# openSX70_ALADDIN_V391SEEED_20180205.net
KiCad netlist of a schematic drawn in EAGLE
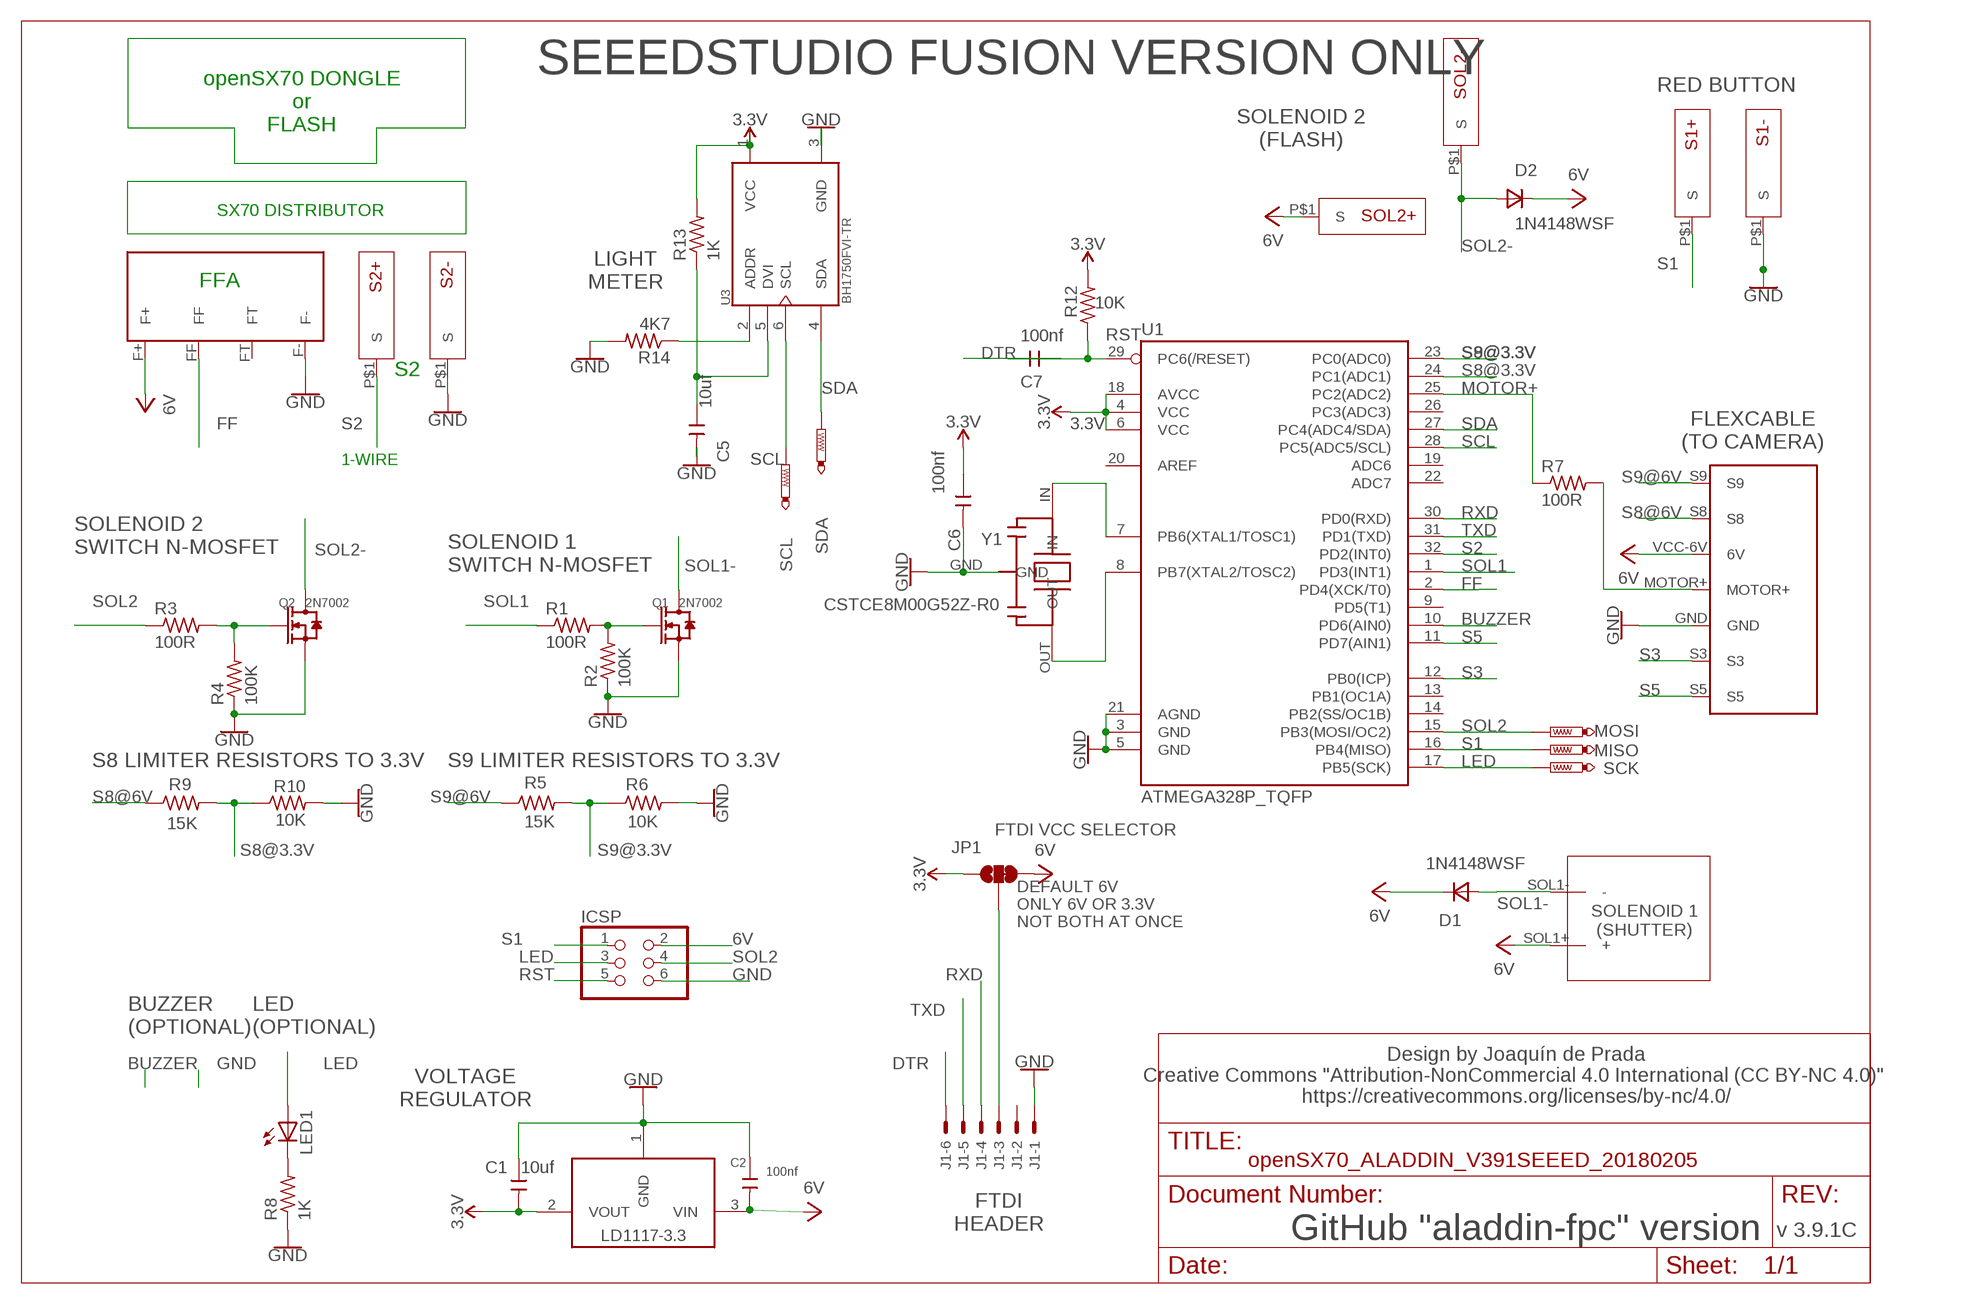
[diagram p0: schematic, sheet 1]

(export (version "E")
  (design (tool "Eeschema 10.0.6"))
  (components
    (comp (ref "C1")
      (value "10uf")
      (footprint "eagle-import:C0603")
      (fields (field (name "MPN") "CC0603KRX5R6BB106"))
      (libsource (lib "eagle-import") (part "CERAMIC-10UF-10V-10%-X5R(0603)"))
    )
    (comp (ref "C2")
      (value "100nf")
      (footprint "eagle-import:C0603")
      (fields (field (name "MPN") "CC0603KRX7R9BB104"))
      (libsource (lib "eagle-import") (part "CERAMIC-100NF-50V-10%-X7R(0603)"))
    )
    (comp (ref "C5")
      (value "10uf")
      (footprint "eagle-import:C0603")
      (fields (field (name "MPN") "CC0603KRX5R6BB106"))
      (libsource (lib "eagle-import") (part "CERAMIC-10UF-10V-10%-X5R(0603)"))
    )
    (comp (ref "C6")
      (value "100nf")
      (footprint "eagle-import:C0603")
      (fields (field (name "MPN") "CC0603KRX7R9BB104"))
      (libsource (lib "eagle-import") (part "CERAMIC-100NF-50V-10%-X7R(0603)"))
    )
    (comp (ref "C7")
      (value "100nf")
      (footprint "eagle-import:C0603")
      (fields (field (name "MPN") "CC0603KRX7R9BB104"))
      (libsource (lib "eagle-import") (part "CERAMIC-100NF-50V-10%-X7R(0603)"))
    )
    (comp (ref "D1")
      (value "1N4148WSF")
      (footprint "eagle-import:SOD323")
      (fields (field (name "MPN") "CDSOD323-T05C"))
      (libsource (lib "eagle-import") (part "DSOD323"))
    )
    (comp (ref "D2")
      (value "1N4148WSF")
      (footprint "eagle-import:SOD323")
      (fields (field (name "MPN") "CDSOD323-T05C"))
      (libsource (lib "eagle-import") (part "DSOD323"))
    )
    (comp (ref "ICSP")
      (value "PINHD-2X3")
      (footprint "eagle-import:2X03")
      (libsource (lib "eagle-import") (part "PINHD-2X3"))
    )
    (comp (ref "J1")
      (value "GND")
      (footprint "eagle-import:XF2L-0625-1")
      (fields (field (name "MF") "OMRON COMPONENTS USA") (field (name "MPN") "XF2L-0625-1"))
      (libsource (lib "eagle-import") (part "XF2-06?25-1L"))
    )
    (comp (ref "JP1")
      (value "FTDI VCC SELECTOR")
      (footprint "eagle-import:SMT-JUMPER_3_1-NC_TRACE_SILK")
      (libsource (lib "eagle-import") (part "JUMPER-SMT_3_1-NC_TRACE_SILK"))
    )
    (comp (ref "LD11172.5V")
      (value "LD1117 2.5V")
      (footprint "eagle-import:SOT223")
      (fields (field (name "MF") "Advanced Monolithic Systems") (field (name "MP") "AMS1117-5.0"))
      (libsource (lib "eagle-import") (part "LD1117-3.3"))
    )
    (comp (ref "LED1")
      (value "LEDCHIPLED_0805")
      (footprint "eagle-import:CHIPLED_0805")
      (libsource (lib "eagle-import") (part "LEDCHIPLED_0805"))
    )
    (comp (ref "MISO")
      (value "PTR1TP08R")
      (footprint "eagle-import:TP08R")
      (libsource (lib "eagle-import") (part "PTR1TP08R"))
    )
    (comp (ref "MOSI")
      (value "PTR1TP08R")
      (footprint "eagle-import:TP08R")
      (libsource (lib "eagle-import") (part "PTR1TP08R"))
    )
    (comp (ref "Q1")
      (value "2N7002")
      (footprint "eagle-import:SOT-23")
      (fields (field (name "MPN") "2N7002,215"))
      (libsource (lib "eagle-import") (part "SMD-MOSFET-N-CH-60V-300MA-LOGIC-LEVEL-FET-2N7002(SOT-23)"))
    )
    (comp (ref "Q2")
      (value "2N7002")
      (footprint "eagle-import:SOT-23")
      (fields (field (name "MPN") "2N7002,215"))
      (libsource (lib "eagle-import") (part "SMD-MOSFET-N-CH-60V-300MA-LOGIC-LEVEL-FET-2N7002(SOT-23)"))
    )
    (comp (ref "R1")
      (value "100R")
      (footprint "eagle-import:R0603")
      (libsource (lib "eagle-import") (part "R-US_R0603"))
    )
    (comp (ref "R2")
      (value "100K")
      (footprint "eagle-import:R0603")
      (libsource (lib "eagle-import") (part "R-US_R0603"))
    )
    (comp (ref "R3")
      (value "100R")
      (footprint "eagle-import:R0603")
      (libsource (lib "eagle-import") (part "R-US_R0603"))
    )
    (comp (ref "R4")
      (value "100K")
      (footprint "eagle-import:R0603")
      (libsource (lib "eagle-import") (part "R-US_R0603"))
    )
    (comp (ref "R5")
      (value "15K")
      (footprint "eagle-import:R0603")
      (libsource (lib "eagle-import") (part "R-US_R0603"))
    )
    (comp (ref "R6")
      (value "10K")
      (footprint "eagle-import:R0603")
      (libsource (lib "eagle-import") (part "R-US_R0603"))
    )
    (comp (ref "R7")
      (value "100R")
      (footprint "eagle-import:R0603")
      (libsource (lib "eagle-import") (part "R-US_R0603"))
    )
    (comp (ref "R8")
      (value "1K")
      (footprint "eagle-import:R0603")
      (libsource (lib "eagle-import") (part "R-US_R0603"))
    )
    (comp (ref "R9")
      (value "15K")
      (footprint "eagle-import:R0603")
      (libsource (lib "eagle-import") (part "R-US_R0603"))
    )
    (comp (ref "R10")
      (value "10K")
      (footprint "eagle-import:R0603")
      (libsource (lib "eagle-import") (part "R-US_R0603"))
    )
    (comp (ref "R12")
      (value "10K")
      (footprint "eagle-import:R0603")
      (libsource (lib "eagle-import") (part "R-US_R0603"))
    )
    (comp (ref "R13")
      (value "1K")
      (footprint "eagle-import:R0603")
      (libsource (lib "eagle-import") (part "R-US_R0603"))
    )
    (comp (ref "R14")
      (value "4K7")
      (footprint "eagle-import:R0603")
      (libsource (lib "eagle-import") (part "R-US_R0603"))
    )
    (comp (ref "S1+")
      (value "SX70-S-PAD-NEW")
      (footprint "eagle-import:SX70-S-PAD2")
      (libsource (lib "eagle-import") (part "SX70-S-PAD-NEW"))
    )
    (comp (ref "S1-")
      (value "SX70-S-PAD-NEW")
      (footprint "eagle-import:SX70-S-PAD2")
      (libsource (lib "eagle-import") (part "SX70-S-PAD-NEW"))
    )
    (comp (ref "S2+")
      (value "SX70-S-PAD-NEW")
      (footprint "eagle-import:SX70-S-PAD2")
      (libsource (lib "eagle-import") (part "SX70-S-PAD-NEW"))
    )
    (comp (ref "S2-")
      (value "SX70-S-PAD-NEW")
      (footprint "eagle-import:SX70-S-PAD2")
      (libsource (lib "eagle-import") (part "SX70-S-PAD-NEW"))
    )
    (comp (ref "SCK")
      (value "PTR1TP08R")
      (footprint "eagle-import:TP08R")
      (libsource (lib "eagle-import") (part "PTR1TP08R"))
    )
    (comp (ref "SCL")
      (value "PTR1TP08R")
      (footprint "eagle-import:TP08R")
      (libsource (lib "eagle-import") (part "PTR1TP08R"))
    )
    (comp (ref "SDA")
      (value "PTR1TP08R")
      (footprint "eagle-import:TP08R")
      (libsource (lib "eagle-import") (part "PTR1TP08R"))
    )
    (comp (ref "SOL1")
      (value "SX70-SOLENOID1-2PADS")
      (footprint "eagle-import:SX70-SOLENOID1-2")
      (libsource (lib "eagle-import") (part "SX70-SOLENOID1-2PADS"))
    )
    (comp (ref "SOL2+")
      (value "SX70-S-PAD-NEW")
      (footprint "eagle-import:SX70-S-PAD2")
      (libsource (lib "eagle-import") (part "SX70-S-PAD-NEW"))
    )
    (comp (ref "SOL2-")
      (value "SX70-S-PAD-NEW")
      (footprint "eagle-import:SX70-S-PAD2")
      (libsource (lib "eagle-import") (part "SX70-S-PAD-NEW"))
    )
    (comp (ref "U$1")
      (value "SX70-7-PAD")
      (footprint "eagle-import:SX70-7-PAD")
      (libsource (lib "eagle-import") (part "SX70-7-PAD"))
    )
    (comp (ref "U$2")
      (value "FFA")
      (footprint "eagle-import:FFA-PAD-PACKAGE")
      (libsource (lib "eagle-import") (part "SX70-FFA-PAD"))
    )
    (comp (ref "U1")
      (value "ATMEGA328P_TQFP")
      (footprint "eagle-import:TQFP32-08")
      (libsource (lib "eagle-import") (part "ATMEGA328P_TQFP"))
    )
    (comp (ref "U3")
      (value "BH1750FVI-TR")
      (footprint "eagle-import:SOTFL50P300X75-6N")
      (fields (field (name "MF") "Rohm"))
      (libsource (lib "eagle-import") (part "BH1750FVI-TR"))
    )
    (comp (ref "Y1")
      (value "CSTCE8M00G52Z-R0")
      (footprint "eagle-import:CFP95P160X100-3N")
      (fields (field (name "MF") "Murata") (field (name "MP") "CSTCE16M0V53-R0"))
      (libsource (lib "eagle-import") (part "CSTCE16M0V53-R0"))
    )
  )
  (nets
    (net (code "1") (name "/BUZZER") (class "Default")
      (node (ref "U1") (pin "10") (pinfunction "PD6(AIN0)_10") (pintype "bidirectional"))
    )
    (net (code "2") (name "/DTR") (class "Default")
      (node (ref "C7") (pin "1") (pinfunction "1_1") (pintype "passive"))
      (node (ref "J1") (pin "6") (pinfunction "MS_6") (pintype "passive"))
    )
    (net (code "3") (name "/FF") (class "Default")
      (node (ref "U$2") (pin "FF") (pinfunction "FF_FF") (pintype "bidirectional"))
      (node (ref "U1") (pin "2") (pinfunction "PD4(XCK/T0)_2") (pintype "bidirectional"))
    )
    (net (code "4") (name "/LED") (class "Default")
      (node (ref "ICSP") (pin "3") (pinfunction "3_3") (pintype "passive"))
      (node (ref "LED1") (pin "A") (pinfunction "A_A") (pintype "passive"))
      (node (ref "SCK") (pin "TP") (pinfunction "TP_TP") (pintype "input"))
      (node (ref "U1") (pin "17") (pinfunction "PB5(SCK)_17") (pintype "bidirectional"))
    )
    (net (code "5") (name "/MOTOR+") (class "Default")
      (node (ref "R7") (pin "1") (pinfunction "1_1") (pintype "passive"))
      (node (ref "U1") (pin "25") (pinfunction "PC2(ADC2)_25") (pintype "bidirectional"))
    )
    (net (code "6") (name "/RST") (class "Default")
      (node (ref "C7") (pin "2") (pinfunction "2_2") (pintype "passive"))
      (node (ref "ICSP") (pin "5") (pinfunction "5_5") (pintype "passive"))
      (node (ref "R12") (pin "1") (pinfunction "1_1") (pintype "passive"))
      (node (ref "U1") (pin "29") (pinfunction "PC6(/RESET)_29") (pintype "bidirectional"))
    )
    (net (code "7") (name "/RXD") (class "Default")
      (node (ref "J1") (pin "4") (pinfunction "MS_4") (pintype "passive"))
      (node (ref "U1") (pin "30") (pinfunction "PD0(RXD)_30") (pintype "bidirectional"))
    )
    (net (code "8") (name "/S1") (class "Default")
      (node (ref "ICSP") (pin "1") (pinfunction "1_1") (pintype "passive"))
      (node (ref "MISO") (pin "TP") (pinfunction "TP_TP") (pintype "input"))
      (node (ref "S1+") (pin "P$1") (pinfunction "S_P$1") (pintype "bidirectional"))
      (node (ref "U1") (pin "16") (pinfunction "PB4(MISO)_16") (pintype "bidirectional"))
    )
    (net (code "9") (name "/S2") (class "Default")
      (node (ref "S2+") (pin "P$1") (pinfunction "S_P$1") (pintype "bidirectional"))
      (node (ref "U1") (pin "32") (pinfunction "PD2(INT0)_32") (pintype "bidirectional"))
    )
    (net (code "10") (name "/S3") (class "Default")
      (node (ref "U$1") (pin "S3") (pinfunction "S3_S3") (pintype "bidirectional"))
      (node (ref "U1") (pin "12") (pinfunction "PB0(ICP)_12") (pintype "bidirectional"))
    )
    (net (code "11") (name "/S5") (class "Default")
      (node (ref "U$1") (pin "S5") (pinfunction "S5_S5") (pintype "bidirectional"))
      (node (ref "U1") (pin "11") (pinfunction "PD7(AIN1)_11") (pintype "bidirectional"))
    )
    (net (code "12") (name "/S8@3.3V") (class "Default")
      (node (ref "R10") (pin "1") (pinfunction "1_1") (pintype "passive"))
      (node (ref "R9") (pin "2") (pinfunction "2_2") (pintype "passive"))
      (node (ref "U1") (pin "24") (pinfunction "PC1(ADC1)_24") (pintype "bidirectional"))
    )
    (net (code "13") (name "/S8@6V") (class "Default")
      (node (ref "R9") (pin "1") (pinfunction "1_1") (pintype "passive"))
      (node (ref "U$1") (pin "S8") (pinfunction "S8_S8") (pintype "bidirectional"))
    )
    (net (code "14") (name "/S9@3.3V") (class "Default")
      (node (ref "R5") (pin "2") (pinfunction "2_2") (pintype "passive"))
      (node (ref "R6") (pin "1") (pinfunction "1_1") (pintype "passive"))
      (node (ref "U1") (pin "23") (pinfunction "PC0(ADC0)_23") (pintype "bidirectional"))
    )
    (net (code "15") (name "/S9@6V") (class "Default")
      (node (ref "R5") (pin "1") (pinfunction "1_1") (pintype "passive"))
      (node (ref "U$1") (pin "S9") (pinfunction "S9_S9") (pintype "bidirectional"))
    )
    (net (code "16") (name "/SCL") (class "Default")
      (node (ref "SCL") (pin "TP") (pinfunction "TP_TP") (pintype "input"))
      (node (ref "U1") (pin "28") (pinfunction "PC5(ADC5/SCL)_28") (pintype "bidirectional"))
      (node (ref "U3") (pin "6") (pinfunction "SCL_6") (pintype "input"))
    )
    (net (code "17") (name "/SDA") (class "Default")
      (node (ref "SDA") (pin "TP") (pinfunction "TP_TP") (pintype "input"))
      (node (ref "U1") (pin "27") (pinfunction "PC4(ADC4/SDA)_27") (pintype "bidirectional"))
      (node (ref "U3") (pin "4") (pinfunction "SDA_4") (pintype "bidirectional"))
    )
    (net (code "18") (name "/SOL1") (class "Default")
      (node (ref "R1") (pin "1") (pinfunction "1_1") (pintype "passive"))
      (node (ref "U1") (pin "1") (pinfunction "PD3(INT1)_1") (pintype "bidirectional"))
    )
    (net (code "19") (name "/SOL1-") (class "Default")
      (node (ref "D1") (pin "2") (pinfunction "A_2") (pintype "passive"))
      (node (ref "Q1") (pin "3") (pinfunction "D_3") (pintype "passive"))
      (node (ref "SOL1") (pin "SOL1-") (pinfunction "-_SOL1-") (pintype "bidirectional"))
    )
    (net (code "20") (name "/SOL2") (class "Default")
      (node (ref "ICSP") (pin "4") (pinfunction "4_4") (pintype "passive"))
      (node (ref "MOSI") (pin "TP") (pinfunction "TP_TP") (pintype "input"))
      (node (ref "R3") (pin "1") (pinfunction "1_1") (pintype "passive"))
      (node (ref "U1") (pin "15") (pinfunction "PB3(MOSI/OC2)_15") (pintype "bidirectional"))
    )
    (net (code "21") (name "/SOL2-") (class "Default")
      (node (ref "D2") (pin "2") (pinfunction "A_2") (pintype "passive"))
      (node (ref "Q2") (pin "3") (pinfunction "D_3") (pintype "passive"))
      (node (ref "SOL2-") (pin "P$1") (pinfunction "S_P$1") (pintype "bidirectional"))
    )
    (net (code "22") (name "/TXD") (class "Default")
      (node (ref "J1") (pin "5") (pinfunction "MS_5") (pintype "passive"))
      (node (ref "U1") (pin "31") (pinfunction "PD1(TXD)_31") (pintype "bidirectional"))
    )
    (net (code "23") (name "3.3V") (class "Default")
      (node (ref "C1") (pin "2") (pinfunction "2_2") (pintype "passive"))
      (node (ref "C6") (pin "1") (pinfunction "1_1") (pintype "passive"))
      (node (ref "JP1") (pin "1") (pinfunction "1_1") (pintype "passive"))
      (node (ref "LD11172.5V") (pin "2") (pinfunction "VOUT_2") (pintype "bidirectional"))
      (node (ref "R12") (pin "2") (pinfunction "2_2") (pintype "passive"))
      (node (ref "R13") (pin "2") (pinfunction "2_2") (pintype "passive"))
      (node (ref "U1") (pin "18") (pinfunction "AVCC_18") (pintype "bidirectional"))
      (node (ref "U1") (pin "4") (pinfunction "VCC_4") (pintype "bidirectional"))
      (node (ref "U1") (pin "6") (pinfunction "VCC_6") (pintype "bidirectional"))
      (node (ref "U3") (pin "1") (pinfunction "VCC_1") (pintype "power_in"))
    )
    (net (code "24") (name "6V") (class "Default")
      (node (ref "C2") (pin "2") (pinfunction "2_2") (pintype "passive"))
      (node (ref "D1") (pin "1") (pinfunction "C_1") (pintype "passive"))
      (node (ref "D2") (pin "1") (pinfunction "C_1") (pintype "passive"))
      (node (ref "ICSP") (pin "2") (pinfunction "2_2") (pintype "passive"))
      (node (ref "JP1") (pin "3") (pinfunction "3_3") (pintype "passive"))
      (node (ref "LD11172.5V") (pin "3") (pinfunction "VIN_3") (pintype "bidirectional"))
      (node (ref "SOL1") (pin "SOL1+") (pinfunction "+_SOL1+") (pintype "bidirectional"))
      (node (ref "SOL2+") (pin "P$1") (pinfunction "S_P$1") (pintype "bidirectional"))
      (node (ref "U$1") (pin "VCC-6V") (pinfunction "6V_VCC-6V") (pintype "bidirectional"))
      (node (ref "U$2") (pin "F+") (pinfunction "F+_F+") (pintype "bidirectional"))
    )
    (net (code "25") (name "GND") (class "Default")
      (node (ref "C1") (pin "1") (pinfunction "1_1") (pintype "passive"))
      (node (ref "C2") (pin "1") (pinfunction "1_1") (pintype "passive"))
      (node (ref "C5") (pin "2") (pinfunction "2_2") (pintype "passive"))
      (node (ref "C6") (pin "2") (pinfunction "2_2") (pintype "passive"))
      (node (ref "ICSP") (pin "6") (pinfunction "6_6") (pintype "passive"))
      (node (ref "J1") (pin "1") (pinfunction "MS_1") (pintype "passive"))
      (node (ref "LD11172.5V") (pin "1") (pinfunction "GND_1") (pintype "bidirectional"))
      (node (ref "Q1") (pin "2") (pinfunction "S_2") (pintype "passive"))
      (node (ref "Q2") (pin "2") (pinfunction "S_2") (pintype "passive"))
      (node (ref "R10") (pin "2") (pinfunction "2_2") (pintype "passive"))
      (node (ref "R14") (pin "2") (pinfunction "2_2") (pintype "passive"))
      (node (ref "R2") (pin "1") (pinfunction "1_1") (pintype "passive"))
      (node (ref "R4") (pin "1") (pinfunction "1_1") (pintype "passive"))
      (node (ref "R6") (pin "2") (pinfunction "2_2") (pintype "passive"))
      (node (ref "R8") (pin "1") (pinfunction "1_1") (pintype "passive"))
      (node (ref "S1-") (pin "P$1") (pinfunction "S_P$1") (pintype "bidirectional"))
      (node (ref "S2-") (pin "P$1") (pinfunction "S_P$1") (pintype "bidirectional"))
      (node (ref "U$1") (pin "GND") (pinfunction "GND_GND") (pintype "bidirectional"))
      (node (ref "U$2") (pin "F-") (pinfunction "F-_F-") (pintype "bidirectional"))
      (node (ref "U1") (pin "21") (pinfunction "AGND_21") (pintype "bidirectional"))
      (node (ref "U1") (pin "3") (pinfunction "GND_3") (pintype "bidirectional"))
      (node (ref "U1") (pin "5") (pinfunction "GND_5") (pintype "bidirectional"))
      (node (ref "U3") (pin "3") (pinfunction "GND_3") (pintype "power_in"))
      (node (ref "Y1") (pin "GND") (pinfunction "GND_GND") (pintype "passive"))
    )
    (net (code "26") (name "Net-(J1C-MS)") (class "Default")
      (node (ref "J1") (pin "3") (pinfunction "MS_3") (pintype "passive"))
      (node (ref "JP1") (pin "2") (pinfunction "2_2") (pintype "passive"))
    )
    (net (code "27") (name "Net-(LED1-PadC)") (class "Default")
      (node (ref "LED1") (pin "C") (pinfunction "C_C") (pintype "passive"))
      (node (ref "R8") (pin "2") (pinfunction "2_2") (pintype "passive"))
    )
    (net (code "28") (name "Net-(Q1-G)") (class "Default")
      (node (ref "Q1") (pin "1") (pinfunction "G_1") (pintype "passive"))
      (node (ref "R1") (pin "2") (pinfunction "2_2") (pintype "passive"))
      (node (ref "R2") (pin "2") (pinfunction "2_2") (pintype "passive"))
    )
    (net (code "29") (name "Net-(Q2-G)") (class "Default")
      (node (ref "Q2") (pin "1") (pinfunction "G_1") (pintype "passive"))
      (node (ref "R3") (pin "2") (pinfunction "2_2") (pintype "passive"))
      (node (ref "R4") (pin "2") (pinfunction "2_2") (pintype "passive"))
    )
    (net (code "30") (name "Net-(R7-Pad2)") (class "Default")
      (node (ref "R7") (pin "2") (pinfunction "2_2") (pintype "passive"))
      (node (ref "U$1") (pin "MOTOR+") (pinfunction "MOTOR+_MOTOR+") (pintype "bidirectional"))
    )
    (net (code "31") (name "Net-(U1-PB6(XTAL1{slash}TOSC1))") (class "Default")
      (node (ref "U1") (pin "7") (pinfunction "PB6(XTAL1/TOSC1)_7") (pintype "bidirectional"))
      (node (ref "Y1") (pin "IN") (pinfunction "IN_IN") (pintype "input"))
    )
    (net (code "32") (name "Net-(U1-PB7(XTAL2{slash}TOSC2))") (class "Default")
      (node (ref "U1") (pin "8") (pinfunction "PB7(XTAL2/TOSC2)_8") (pintype "bidirectional"))
      (node (ref "Y1") (pin "OUT") (pinfunction "OUT_OUT") (pintype "output"))
    )
    (net (code "33") (name "Net-(U3-ADDR)") (class "Default")
      (node (ref "R14") (pin "1") (pinfunction "1_1") (pintype "passive"))
      (node (ref "U3") (pin "2") (pinfunction "ADDR_2") (pintype "input"))
    )
    (net (code "34") (name "Net-(U3-DVI)") (class "Default")
      (node (ref "C5") (pin "1") (pinfunction "1_1") (pintype "passive"))
      (node (ref "R13") (pin "1") (pinfunction "1_1") (pintype "passive"))
      (node (ref "U3") (pin "5") (pinfunction "DVI_5") (pintype "input"))
    )
    (net (code "35") (name "unconnected-(J1B-MS-Pad2)") (class "Default")
      (node (ref "J1") (pin "2") (pinfunction "MS_2") (pintype "passive"))
    )
    (net (code "36") (name "unconnected-(U$2-PadFT)") (class "Default")
      (node (ref "U$2") (pin "FT") (pinfunction "FT_FT") (pintype "bidirectional"))
    )
    (net (code "37") (name "unconnected-(U1-ADC6-Pad19)") (class "Default")
      (node (ref "U1") (pin "19") (pinfunction "ADC6_19") (pintype "bidirectional"))
    )
    (net (code "38") (name "unconnected-(U1-ADC7-Pad22)") (class "Default")
      (node (ref "U1") (pin "22") (pinfunction "ADC7_22") (pintype "bidirectional"))
    )
    (net (code "39") (name "unconnected-(U1-AREF-Pad20)") (class "Default")
      (node (ref "U1") (pin "20") (pinfunction "AREF_20") (pintype "bidirectional"))
    )
    (net (code "40") (name "unconnected-(U1-PB1(OC1A)-Pad13)") (class "Default")
      (node (ref "U1") (pin "13") (pinfunction "PB1(OC1A)_13") (pintype "bidirectional"))
    )
    (net (code "41") (name "unconnected-(U1-PB2(SS{slash}OC1B)-Pad14)") (class "Default")
      (node (ref "U1") (pin "14") (pinfunction "PB2(SS/OC1B)_14") (pintype "bidirectional"))
    )
    (net (code "42") (name "unconnected-(U1-PC3(ADC3)-Pad26)") (class "Default")
      (node (ref "U1") (pin "26") (pinfunction "PC3(ADC3)_26") (pintype "bidirectional"))
    )
    (net (code "43") (name "unconnected-(U1-PD5(T1)-Pad9)") (class "Default")
      (node (ref "U1") (pin "9") (pinfunction "PD5(T1)_9") (pintype "bidirectional"))
    )
  )
)
